# clock.net
KiCad netlist of a schematic drawn in Altium Designer
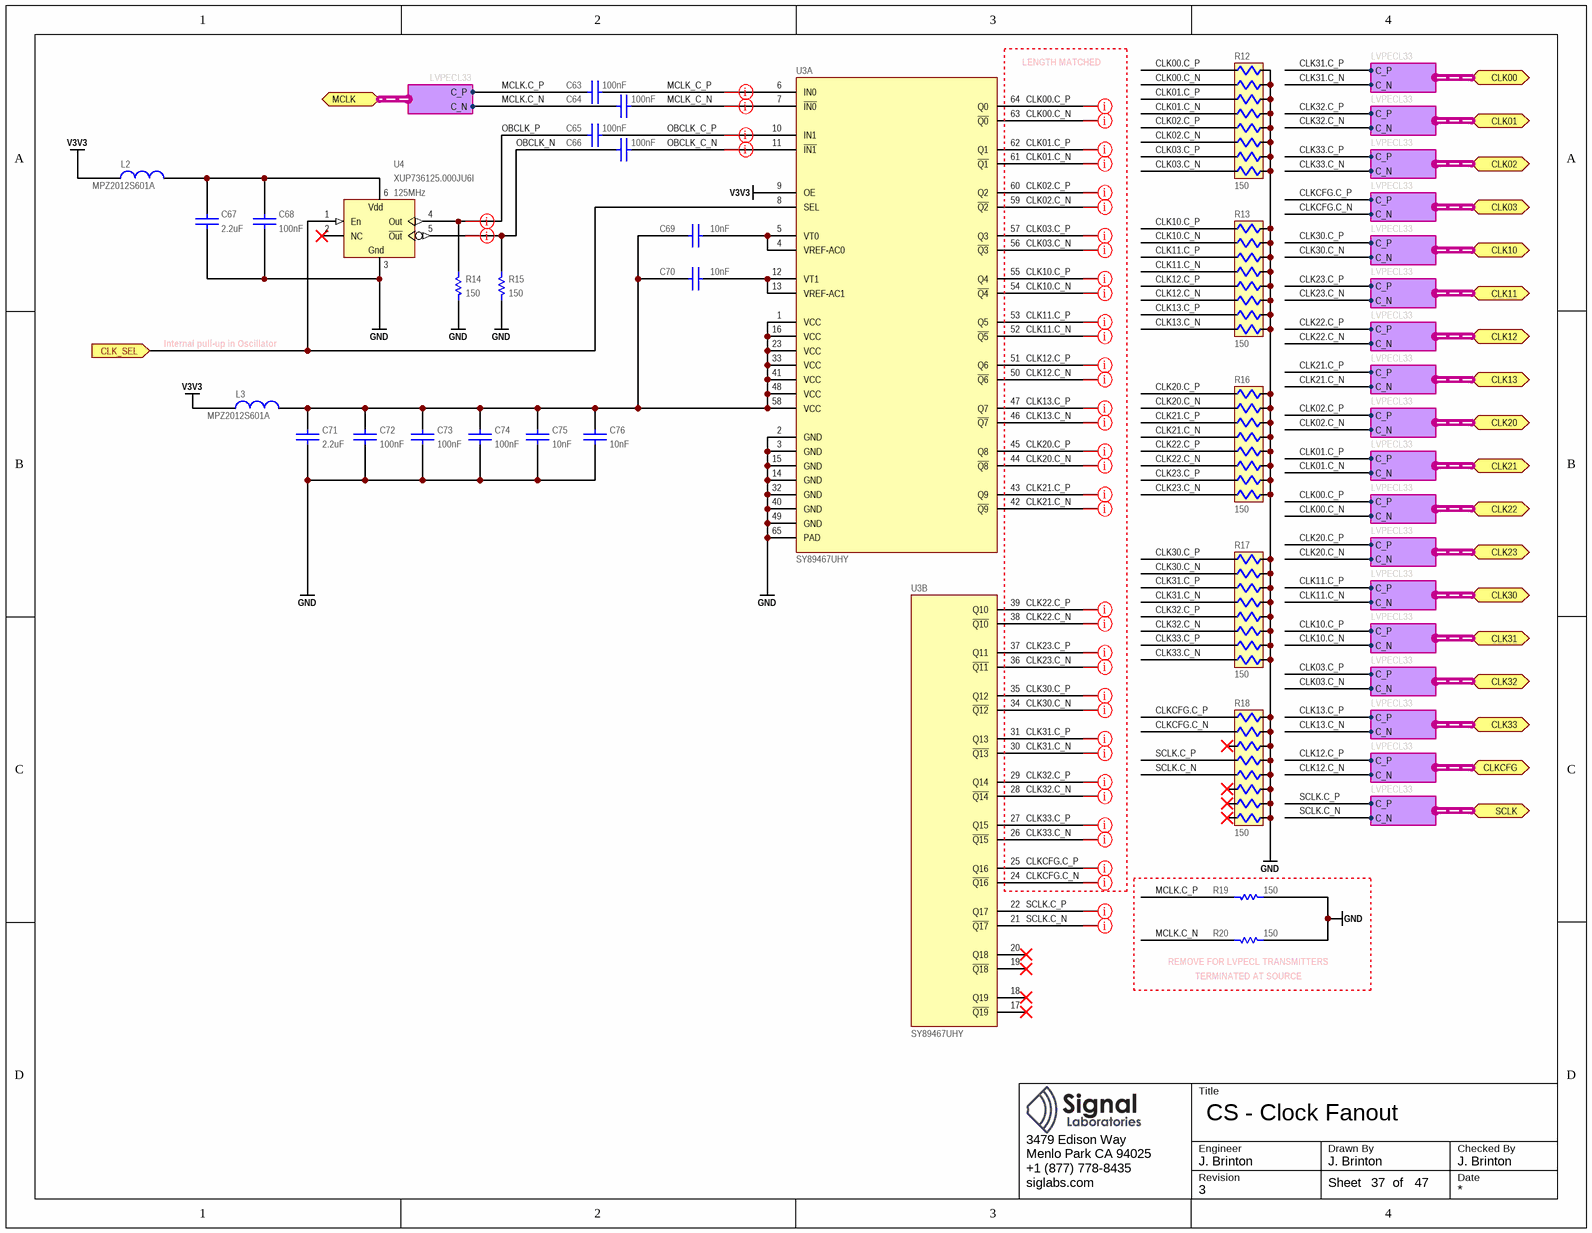
[diagram p0: clock.SchDoc]

(export (version "E")
  (design (tool "Eeschema 10.0.6"))
  (components
    (comp (ref "C63")
      (value "100nF")
      (footprint "CAPC100X50X55L25N")
      (description "Ceramic Capacitor 100nF ±10% 50V X7R 0402")
      (fields (field (name "MANUFACTURER") "Murata") (field (name "TOLERANCE") "±10%"))
      (libsource (lib "generic") (part "CAP"))
    )
    (comp (ref "C64")
      (value "100nF")
      (footprint "CAPC100X50X55L25N")
      (description "Ceramic Capacitor 100nF ±10% 50V X7R 0402")
      (fields (field (name "MANUFACTURER") "Murata") (field (name "TOLERANCE") "±10%"))
      (libsource (lib "generic") (part "CAP"))
    )
    (comp (ref "C65")
      (value "100nF")
      (footprint "CAPC100X50X55L25N")
      (description "Ceramic Capacitor 100nF ±10% 50V X7R 0402")
      (fields (field (name "MANUFACTURER") "Murata") (field (name "TOLERANCE") "±10%"))
      (libsource (lib "generic") (part "CAP"))
    )
    (comp (ref "C66")
      (value "100nF")
      (footprint "CAPC100X50X55L25N")
      (description "Ceramic Capacitor 100nF ±10% 50V X7R 0402")
      (fields (field (name "MANUFACTURER") "Murata") (field (name "TOLERANCE") "±10%"))
      (libsource (lib "generic") (part "CAP"))
    )
    (comp (ref "C67")
      (value "2.2uF")
      (footprint "CAPC160X80X90L20N")
      (description "Ceramic Capacitor 2.2uF ±20% 10V X7R 0603")
      (fields (field (name "MANUFACTURER") "TDK") (field (name "TOLERANCE") "±20%"))
      (libsource (lib "generic") (part "CAP"))
    )
    (comp (ref "C68")
      (value "100nF")
      (footprint "CAPC100X50X55L25N")
      (description "Ceramic Capacitor 100nF ±10% 50V X7R 0402")
      (fields (field (name "MANUFACTURER") "Murata") (field (name "TOLERANCE") "±10%"))
      (libsource (lib "generic") (part "CAP"))
    )
    (comp (ref "C69")
      (value "10nF")
      (footprint "CAPC100X50X55L25N")
      (description "Ceramic Capacitor 10nF ±10% 50V X7R 0402")
      (fields (field (name "MANUFACTURER") "Murata") (field (name "TOLERANCE") "±10%"))
      (libsource (lib "") (part "CAP_1"))
    )
    (comp (ref "C70")
      (value "10nF")
      (footprint "CAPC100X50X55L25N")
      (description "Ceramic Capacitor 10nF ±10% 50V X7R 0402")
      (fields (field (name "MANUFACTURER") "Murata") (field (name "TOLERANCE") "±10%"))
      (libsource (lib "") (part "CAP_1"))
    )
    (comp (ref "C71")
      (value "2.2uF")
      (footprint "CAPC160X80X90L20N")
      (description "Ceramic Capacitor 2.2uF ±20% 10V X7R 0603")
      (fields (field (name "MANUFACTURER") "TDK") (field (name "TOLERANCE") "±20%"))
      (libsource (lib "generic") (part "CAP"))
    )
    (comp (ref "C72")
      (value "100nF")
      (footprint "CAPC100X50X55L25N")
      (description "Ceramic Capacitor 100nF ±10% 50V X7R 0402")
      (fields (field (name "MANUFACTURER") "Murata") (field (name "TOLERANCE") "±10%"))
      (libsource (lib "generic") (part "CAP"))
    )
    (comp (ref "C73")
      (value "100nF")
      (footprint "CAPC100X50X55L25N")
      (description "Ceramic Capacitor 100nF ±10% 50V X7R 0402")
      (fields (field (name "MANUFACTURER") "Murata") (field (name "TOLERANCE") "±10%"))
      (libsource (lib "generic") (part "CAP"))
    )
    (comp (ref "C74")
      (value "100nF")
      (footprint "CAPC100X50X55L25N")
      (description "Ceramic Capacitor 100nF ±10% 50V X7R 0402")
      (fields (field (name "MANUFACTURER") "Murata") (field (name "TOLERANCE") "±10%"))
      (libsource (lib "generic") (part "CAP"))
    )
    (comp (ref "C75")
      (value "10nF")
      (footprint "CAPC100X50X55L25N")
      (description "Ceramic Capacitor 10nF ±10% 50V X7R 0402")
      (fields (field (name "MANUFACTURER") "Murata") (field (name "TOLERANCE") "±10%"))
      (libsource (lib "") (part "CAP_1"))
    )
    (comp (ref "C76")
      (value "10nF")
      (footprint "CAPC100X50X55L25N")
      (description "Ceramic Capacitor 10nF ±10% 50V X7R 0402")
      (fields (field (name "MANUFACTURER") "Murata") (field (name "TOLERANCE") "±10%"))
      (libsource (lib "") (part "CAP_1"))
    )
    (comp (ref "L2")
      (value "MPZ2012S601A")
      (footprint "0805")
      (description "Ferrite Bead 600-Ohm @ 100 MHz 2A 0805")
      (fields (field (name "MANUFACTURER") "TDK"))
      (libsource (lib "*") (part "INDUCTANCE1"))
    )
    (comp (ref "L3")
      (value "MPZ2012S601A")
      (footprint "0805")
      (description "Ferrite Bead 600-Ohm @ 100 MHz 2A 0805")
      (fields (field (name "MANUFACTURER") "TDK"))
      (libsource (lib "*") (part "INDUCTANCE1"))
    )
    (comp (ref "R12")
      (value "150")
      (footprint "RESCAXE16P50_380X160X55L30X35N")
      (description "8 Resistor Array 150 ±5% 0.0625W 25V 1506")
      (fields (field (name "MANUFACTURER") "Panasonic") (field (name "TOLERANCE") "±5%"))
      (libsource (lib "altium-import") (part "root_0_EXB-2HV470JV_"))
    )
    (comp (ref "R13")
      (value "150")
      (footprint "RESCAXE16P50_380X160X55L30X35N")
      (description "8 Resistor Array 150 ±5% 0.0625W 25V 1506")
      (fields (field (name "MANUFACTURER") "Panasonic") (field (name "TOLERANCE") "±5%"))
      (libsource (lib "altium-import") (part "root_0_EXB-2HV470JV_"))
    )
    (comp (ref "R14")
      (value "150")
      (footprint "RESC1005X40N")
      (description "Thick Film Resistor 150 ±1% 0.1W 50V 0402")
      (fields (field (name "TOLERANCE") "±1%") (field (name "MANUFACTURER") "Panasonic"))
      (libsource (lib "generic") (part "RES"))
    )
    (comp (ref "R15")
      (value "150")
      (footprint "RESC1005X40N")
      (description "Thick Film Resistor 150 ±1% 0.1W 50V 0402")
      (fields (field (name "TOLERANCE") "±1%") (field (name "MANUFACTURER") "Panasonic"))
      (libsource (lib "generic") (part "RES"))
    )
    (comp (ref "R16")
      (value "150")
      (footprint "RESCAXE16P50_380X160X55L30X35N")
      (description "8 Resistor Array 150 ±5% 0.0625W 25V 1506")
      (fields (field (name "MANUFACTURER") "Panasonic") (field (name "TOLERANCE") "±5%"))
      (libsource (lib "altium-import") (part "root_0_EXB-2HV470JV_"))
    )
    (comp (ref "R17")
      (value "150")
      (footprint "RESCAXE16P50_380X160X55L30X35N")
      (description "8 Resistor Array 150 ±5% 0.0625W 25V 1506")
      (fields (field (name "MANUFACTURER") "Panasonic") (field (name "TOLERANCE") "±5%"))
      (libsource (lib "altium-import") (part "root_0_EXB-2HV470JV_"))
    )
    (comp (ref "R18")
      (value "150")
      (footprint "RESCAXE16P50_380X160X55L30X35N")
      (description "8 Resistor Array 150 ±5% 0.0625W 25V 1506")
      (fields (field (name "MANUFACTURER") "Panasonic") (field (name "TOLERANCE") "±5%"))
      (libsource (lib "altium-import") (part "root_0_EXB-2HV470JV_"))
    )
    (comp (ref "R19")
      (value "150")
      (footprint "RESC1005X40N")
      (description "Thick Film Resistor 150 ±1% 0.1W 50V 0402")
      (fields (field (name "TOLERANCE") "±1%") (field (name "MANUFACTURER") "Panasonic"))
      (libsource (lib "generic") (part "RES"))
    )
    (comp (ref "R20")
      (value "150")
      (footprint "RESC1005X40N")
      (description "Thick Film Resistor 150 ±1% 0.1W 50V 0402")
      (fields (field (name "TOLERANCE") "±1%") (field (name "MANUFACTURER") "Panasonic"))
      (libsource (lib "generic") (part "RES"))
    )
    (comp (ref "U3")
      (value "SY89467UHY")
      (footprint "QFP65P50_1200X1200X120L60X22T500N")
      (description "2:20 LVPECL Clock Distribution Driver")
      (fields (field (name "MANUFACTURER") "Microchip"))
      (libsource (lib "microchip") (part "SY89467UHY"))
    )
    (comp (ref "U4")
      (value "125MHz")
      (footprint "fox:OSCSC6P254_735X505X140L110X140")
      (description "Oscillator 100MHz LPECL 3.3V 25ppm SMD")
      (fields
        (field (name "MANUFACTURER") "IDT")
        (field (name "MANUFACTURER P/N") "XUP736125.000JU6I")
        (field (name "Comment") "XUP736125.000JU6I")
      )
      (libsource (lib "seiko") (part "EG-2121CA 100.0000M-PHPAB"))
    )
  )
  (nets
    (net (code "2") (name "/CLK00.C_N") (class "Default")
      (node (ref "R12") (pin "2") (pinfunction "2_2") (pintype "passive"))
      (node (ref "U3") (pin "63") (pinfunction "~{Q0}_63") (pintype "passive"))
    )
    (net (code "3") (name "/CLK00.C_P") (class "Default")
      (node (ref "R12") (pin "1") (pintype "passive"))
      (node (ref "U3") (pin "64") (pinfunction "Q0_64") (pintype "passive"))
    )
    (net (code "4") (name "/CLK01.C_N") (class "Default")
      (node (ref "R12") (pin "4") (pinfunction "4_4") (pintype "passive"))
      (node (ref "U3") (pin "61") (pinfunction "~{Q1}_61") (pintype "passive"))
    )
    (net (code "5") (name "/CLK01.C_P") (class "Default")
      (node (ref "R12") (pin "3") (pinfunction "3_3") (pintype "passive"))
      (node (ref "U3") (pin "62") (pinfunction "Q1_62") (pintype "passive"))
    )
    (net (code "6") (name "/CLK02.C_N") (class "Default")
      (node (ref "R12") (pin "6") (pinfunction "6_6") (pintype "passive"))
      (node (ref "U3") (pin "59") (pinfunction "~{Q2}_59") (pintype "passive"))
    )
    (net (code "7") (name "/CLK02.C_P") (class "Default")
      (node (ref "R12") (pin "5") (pinfunction "5_5") (pintype "passive"))
      (node (ref "U3") (pin "60") (pinfunction "Q2_60") (pintype "passive"))
    )
    (net (code "8") (name "/CLK03.C_N") (class "Default")
      (node (ref "R12") (pin "8") (pinfunction "8_8") (pintype "passive"))
      (node (ref "U3") (pin "56") (pinfunction "~{Q3}_56") (pintype "passive"))
    )
    (net (code "9") (name "/CLK03.C_P") (class "Default")
      (node (ref "R12") (pin "7") (pinfunction "7_7") (pintype "passive"))
      (node (ref "U3") (pin "57") (pinfunction "Q3_57") (pintype "passive"))
    )
    (net (code "10") (name "/CLK10.C_N") (class "Default")
      (node (ref "R13") (pin "2") (pinfunction "2_2") (pintype "passive"))
      (node (ref "U3") (pin "54") (pinfunction "~{Q4}_54") (pintype "passive"))
    )
    (net (code "11") (name "/CLK10.C_P") (class "Default")
      (node (ref "R13") (pin "1") (pintype "passive"))
      (node (ref "U3") (pin "55") (pinfunction "Q4_55") (pintype "passive"))
    )
    (net (code "12") (name "/CLK11.C_N") (class "Default")
      (node (ref "R13") (pin "4") (pinfunction "4_4") (pintype "passive"))
      (node (ref "U3") (pin "52") (pinfunction "~{Q5}_52") (pintype "passive"))
    )
    (net (code "13") (name "/CLK11.C_P") (class "Default")
      (node (ref "R13") (pin "3") (pinfunction "3_3") (pintype "passive"))
      (node (ref "U3") (pin "53") (pinfunction "Q5_53") (pintype "passive"))
    )
    (net (code "14") (name "/CLK12.C_N") (class "Default")
      (node (ref "R13") (pin "6") (pinfunction "6_6") (pintype "passive"))
      (node (ref "U3") (pin "50") (pinfunction "~{Q6}_50") (pintype "passive"))
    )
    (net (code "15") (name "/CLK12.C_P") (class "Default")
      (node (ref "R13") (pin "5") (pinfunction "5_5") (pintype "passive"))
      (node (ref "U3") (pin "51") (pinfunction "Q6_51") (pintype "passive"))
    )
    (net (code "16") (name "/CLK13.C_N") (class "Default")
      (node (ref "R13") (pin "8") (pinfunction "8_8") (pintype "passive"))
      (node (ref "U3") (pin "46") (pinfunction "~{Q7}_46") (pintype "passive"))
    )
    (net (code "17") (name "/CLK13.C_P") (class "Default")
      (node (ref "R13") (pin "7") (pinfunction "7_7") (pintype "passive"))
      (node (ref "U3") (pin "47") (pinfunction "Q7_47") (pintype "passive"))
    )
    (net (code "18") (name "/CLK20.C_N") (class "Default")
      (node (ref "R16") (pin "2") (pinfunction "2_2") (pintype "passive"))
      (node (ref "U3") (pin "44") (pinfunction "~{Q8}_44") (pintype "passive"))
    )
    (net (code "19") (name "/CLK20.C_P") (class "Default")
      (node (ref "R16") (pin "1") (pintype "passive"))
      (node (ref "U3") (pin "45") (pinfunction "Q8_45") (pintype "passive"))
    )
    (net (code "20") (name "/CLK21.C_N") (class "Default")
      (node (ref "R16") (pin "4") (pinfunction "4_4") (pintype "passive"))
      (node (ref "U3") (pin "42") (pinfunction "~{Q9}_42") (pintype "passive"))
    )
    (net (code "21") (name "/CLK21.C_P") (class "Default")
      (node (ref "R16") (pin "3") (pinfunction "3_3") (pintype "passive"))
      (node (ref "U3") (pin "43") (pinfunction "Q9_43") (pintype "passive"))
    )
    (net (code "22") (name "/CLK22.C_N") (class "Default")
      (node (ref "R16") (pin "6") (pinfunction "6_6") (pintype "passive"))
      (node (ref "U3") (pin "38") (pinfunction "~{Q10}_38") (pintype "passive"))
    )
    (net (code "23") (name "/CLK22.C_P") (class "Default")
      (node (ref "R16") (pin "5") (pinfunction "5_5") (pintype "passive"))
      (node (ref "U3") (pin "39") (pinfunction "Q10_39") (pintype "passive"))
    )
    (net (code "24") (name "/CLK23.C_N") (class "Default")
      (node (ref "R16") (pin "8") (pinfunction "8_8") (pintype "passive"))
      (node (ref "U3") (pin "36") (pinfunction "~{Q11}_36") (pintype "passive"))
    )
    (net (code "25") (name "/CLK23.C_P") (class "Default")
      (node (ref "R16") (pin "7") (pinfunction "7_7") (pintype "passive"))
      (node (ref "U3") (pin "37") (pinfunction "Q11_37") (pintype "passive"))
    )
    (net (code "26") (name "/CLK30.C_N") (class "Default")
      (node (ref "R17") (pin "2") (pinfunction "2_2") (pintype "passive"))
      (node (ref "U3") (pin "34") (pinfunction "~{Q12}_34") (pintype "passive"))
    )
    (net (code "27") (name "/CLK30.C_P") (class "Default")
      (node (ref "R17") (pin "1") (pintype "passive"))
      (node (ref "U3") (pin "35") (pinfunction "Q12_35") (pintype "passive"))
    )
    (net (code "28") (name "/CLK31.C_N") (class "Default")
      (node (ref "R17") (pin "4") (pinfunction "4_4") (pintype "passive"))
      (node (ref "U3") (pin "30") (pinfunction "~{Q13}_30") (pintype "passive"))
    )
    (net (code "29") (name "/CLK31.C_P") (class "Default")
      (node (ref "R17") (pin "3") (pinfunction "3_3") (pintype "passive"))
      (node (ref "U3") (pin "31") (pinfunction "Q13_31") (pintype "passive"))
    )
    (net (code "30") (name "/CLK32.C_N") (class "Default")
      (node (ref "R17") (pin "6") (pinfunction "6_6") (pintype "passive"))
      (node (ref "U3") (pin "28") (pinfunction "~{Q14}_28") (pintype "passive"))
    )
    (net (code "31") (name "/CLK32.C_P") (class "Default")
      (node (ref "R17") (pin "5") (pinfunction "5_5") (pintype "passive"))
      (node (ref "U3") (pin "29") (pinfunction "Q14_29") (pintype "passive"))
    )
    (net (code "32") (name "/CLK33.C_N") (class "Default")
      (node (ref "R17") (pin "8") (pinfunction "8_8") (pintype "passive"))
      (node (ref "U3") (pin "26") (pinfunction "~{Q15}_26") (pintype "passive"))
    )
    (net (code "33") (name "/CLK33.C_P") (class "Default")
      (node (ref "R17") (pin "7") (pinfunction "7_7") (pintype "passive"))
      (node (ref "U3") (pin "27") (pinfunction "Q15_27") (pintype "passive"))
    )
    (net (code "34") (name "/CLKCFG.C_N") (class "Default")
      (node (ref "R18") (pin "2") (pinfunction "2_2") (pintype "passive"))
      (node (ref "U3") (pin "24") (pinfunction "~{Q16}_24") (pintype "passive"))
    )
    (net (code "35") (name "/CLKCFG.C_P") (class "Default")
      (node (ref "R18") (pin "1") (pintype "passive"))
      (node (ref "U3") (pin "25") (pinfunction "Q16_25") (pintype "passive"))
    )
    (net (code "36") (name "/CLK_SEL") (class "Default")
      (node (ref "U3") (pin "8") (pinfunction "SEL_8") (pintype "passive"))
      (node (ref "U4") (pin "1") (pinfunction "En_1") (pintype "input"))
    )
    (net (code "37") (name "/MCLK.C_N") (class "Default")
      (node (ref "C64") (pin "2") (pinfunction "2_2") (pintype "passive"))
      (node (ref "R20") (pin "1") (pinfunction "1_1") (pintype "passive"))
    )
    (net (code "38") (name "/MCLK.C_P") (class "Default")
      (node (ref "C63") (pin "2") (pinfunction "2_2") (pintype "passive"))
      (node (ref "R19") (pin "1") (pinfunction "1_1") (pintype "passive"))
    )
    (net (code "39") (name "/MCLK_C_N") (class "Default")
      (node (ref "C64") (pin "1") (pinfunction "1_1") (pintype "passive"))
      (node (ref "U3") (pin "7") (pinfunction "~{IN0}_7") (pintype "passive"))
    )
    (net (code "40") (name "/MCLK_C_P") (class "Default")
      (node (ref "C63") (pin "1") (pinfunction "1_1") (pintype "passive"))
      (node (ref "U3") (pin "6") (pinfunction "IN0_6") (pintype "passive"))
    )
    (net (code "41") (name "/OBCLK_C_N") (class "Default")
      (node (ref "C66") (pin "1") (pinfunction "1_1") (pintype "passive"))
      (node (ref "U3") (pin "11") (pinfunction "~{IN1}_11") (pintype "passive"))
    )
    (net (code "42") (name "/OBCLK_C_P") (class "Default")
      (node (ref "C65") (pin "1") (pinfunction "1_1") (pintype "passive"))
      (node (ref "U3") (pin "10") (pinfunction "IN1_10") (pintype "passive"))
    )
    (net (code "43") (name "/OBCLK_N") (class "Default")
      (node (ref "C66") (pin "2") (pinfunction "2_2") (pintype "passive"))
      (node (ref "R15") (pin "2") (pinfunction "2_2") (pintype "passive"))
      (node (ref "U4") (pin "5") (pinfunction "~{Out}_5") (pintype "output"))
    )
    (net (code "44") (name "/OBCLK_P") (class "Default")
      (node (ref "C65") (pin "2") (pinfunction "2_2") (pintype "passive"))
      (node (ref "R14") (pin "2") (pinfunction "2_2") (pintype "passive"))
      (node (ref "U4") (pin "4") (pinfunction "Out_4") (pintype "output"))
    )
    (net (code "45") (name "/SCLK.C_N") (class "Default")
      (node (ref "R18") (pin "5") (pinfunction "5_5") (pintype "passive"))
      (node (ref "U3") (pin "21") (pinfunction "~{Q17}_21") (pintype "passive"))
    )
    (net (code "46") (name "/SCLK.C_P") (class "Default")
      (node (ref "R18") (pin "4") (pinfunction "4_4") (pintype "passive"))
      (node (ref "U3") (pin "22") (pinfunction "Q17_22") (pintype "passive"))
    )
    (net (code "48") (name "GND") (class "Default")
      (node (ref "C67") (pin "1") (pinfunction "1_1") (pintype "passive"))
      (node (ref "C68") (pin "1") (pinfunction "1_1") (pintype "passive"))
      (node (ref "C71") (pin "1") (pinfunction "1_1") (pintype "passive"))
      (node (ref "C72") (pin "1") (pinfunction "1_1") (pintype "passive"))
      (node (ref "C73") (pin "1") (pinfunction "1_1") (pintype "passive"))
      (node (ref "C74") (pin "1") (pinfunction "1_1") (pintype "passive"))
      (node (ref "C75") (pin "2") (pinfunction "2_2") (pintype "passive"))
      (node (ref "C76") (pin "2") (pinfunction "2_2") (pintype "passive"))
      (node (ref "R12") (pin "10") (pinfunction "10_10") (pintype "passive"))
      (node (ref "R12") (pin "11") (pinfunction "11_11") (pintype "passive"))
      (node (ref "R12") (pin "12") (pinfunction "12_12") (pintype "passive"))
      (node (ref "R12") (pin "13") (pinfunction "13_13") (pintype "passive"))
      (node (ref "R12") (pin "14") (pinfunction "14_14") (pintype "passive"))
      (node (ref "R12") (pin "15") (pinfunction "15_15") (pintype "passive"))
      (node (ref "R12") (pin "16") (pinfunction "16_16") (pintype "passive"))
      (node (ref "R12") (pin "9") (pinfunction "9_9") (pintype "passive"))
      (node (ref "R13") (pin "10") (pinfunction "10_10") (pintype "passive"))
      (node (ref "R13") (pin "11") (pinfunction "11_11") (pintype "passive"))
      (node (ref "R13") (pin "12") (pinfunction "12_12") (pintype "passive"))
      (node (ref "R13") (pin "13") (pinfunction "13_13") (pintype "passive"))
      (node (ref "R13") (pin "14") (pinfunction "14_14") (pintype "passive"))
      (node (ref "R13") (pin "15") (pinfunction "15_15") (pintype "passive"))
      (node (ref "R13") (pin "16") (pinfunction "16_16") (pintype "passive"))
      (node (ref "R13") (pin "9") (pinfunction "9_9") (pintype "passive"))
      (node (ref "R14") (pin "1") (pinfunction "1_1") (pintype "passive"))
      (node (ref "R15") (pin "1") (pinfunction "1_1") (pintype "passive"))
      (node (ref "R16") (pin "10") (pinfunction "10_10") (pintype "passive"))
      (node (ref "R16") (pin "11") (pinfunction "11_11") (pintype "passive"))
      (node (ref "R16") (pin "12") (pinfunction "12_12") (pintype "passive"))
      (node (ref "R16") (pin "13") (pinfunction "13_13") (pintype "passive"))
      (node (ref "R16") (pin "14") (pinfunction "14_14") (pintype "passive"))
      (node (ref "R16") (pin "15") (pinfunction "15_15") (pintype "passive"))
      (node (ref "R16") (pin "16") (pinfunction "16_16") (pintype "passive"))
      (node (ref "R16") (pin "9") (pinfunction "9_9") (pintype "passive"))
      (node (ref "R17") (pin "10") (pinfunction "10_10") (pintype "passive"))
      (node (ref "R17") (pin "11") (pinfunction "11_11") (pintype "passive"))
      (node (ref "R17") (pin "12") (pinfunction "12_12") (pintype "passive"))
      (node (ref "R17") (pin "13") (pinfunction "13_13") (pintype "passive"))
      (node (ref "R17") (pin "14") (pinfunction "14_14") (pintype "passive"))
      (node (ref "R17") (pin "15") (pinfunction "15_15") (pintype "passive"))
      (node (ref "R17") (pin "16") (pinfunction "16_16") (pintype "passive"))
      (node (ref "R17") (pin "9") (pinfunction "9_9") (pintype "passive"))
      (node (ref "R18") (pin "10") (pinfunction "10_10") (pintype "passive"))
      (node (ref "R18") (pin "11") (pinfunction "11_11") (pintype "passive"))
      (node (ref "R18") (pin "12") (pinfunction "12_12") (pintype "passive"))
      (node (ref "R18") (pin "13") (pinfunction "13_13") (pintype "passive"))
      (node (ref "R18") (pin "14") (pinfunction "14_14") (pintype "passive"))
      (node (ref "R18") (pin "15") (pinfunction "15_15") (pintype "passive"))
      (node (ref "R18") (pin "16") (pinfunction "16_16") (pintype "passive"))
      (node (ref "R18") (pin "9") (pinfunction "9_9") (pintype "passive"))
      (node (ref "R19") (pin "2") (pinfunction "2_2") (pintype "passive"))
      (node (ref "R20") (pin "2") (pinfunction "2_2") (pintype "passive"))
      (node (ref "U3") (pin "14") (pinfunction "GND_14") (pintype "passive"))
      (node (ref "U3") (pin "15") (pinfunction "GND_15") (pintype "passive"))
      (node (ref "U3") (pin "2") (pinfunction "GND_2") (pintype "passive"))
      (node (ref "U3") (pin "3") (pinfunction "GND_3") (pintype "passive"))
      (node (ref "U3") (pin "32") (pinfunction "GND_32") (pintype "passive"))
      (node (ref "U3") (pin "40") (pinfunction "GND_40") (pintype "passive"))
      (node (ref "U3") (pin "49") (pinfunction "GND_49") (pintype "passive"))
      (node (ref "U3") (pin "65") (pinfunction "PAD_65") (pintype "passive"))
      (node (ref "U4") (pin "3") (pinfunction "GND_3") (pintype "power_in"))
    )
    (net (code "49") (name "Net-(C69-Pad1)") (class "Default")
      (node (ref "C69") (pin "1") (pinfunction "1_1") (pintype "passive"))
      (node (ref "C70") (pin "1") (pinfunction "1_1") (pintype "passive"))
      (node (ref "C71") (pin "2") (pinfunction "2_2") (pintype "passive"))
      (node (ref "C72") (pin "2") (pinfunction "2_2") (pintype "passive"))
      (node (ref "C73") (pin "2") (pinfunction "2_2") (pintype "passive"))
      (node (ref "C74") (pin "2") (pinfunction "2_2") (pintype "passive"))
      (node (ref "C75") (pin "1") (pinfunction "1_1") (pintype "passive"))
      (node (ref "C76") (pin "1") (pinfunction "1_1") (pintype "passive"))
      (node (ref "L3") (pin "1") (pinfunction "1_1") (pintype "passive"))
      (node (ref "U3") (pin "1") (pinfunction "VCC_1") (pintype "passive"))
      (node (ref "U3") (pin "16") (pinfunction "VCC_16") (pintype "passive"))
      (node (ref "U3") (pin "23") (pinfunction "VCC_23") (pintype "passive"))
      (node (ref "U3") (pin "33") (pinfunction "VCC_33") (pintype "passive"))
      (node (ref "U3") (pin "41") (pinfunction "VCC_41") (pintype "passive"))
      (node (ref "U3") (pin "48") (pinfunction "VCC_48") (pintype "passive"))
      (node (ref "U3") (pin "58") (pinfunction "VCC_58") (pintype "passive"))
    )
    (net (code "50") (name "Net-(U3A-VREF-AC0)") (class "Default")
      (node (ref "C69") (pin "2") (pinfunction "2_2") (pintype "passive"))
      (node (ref "U3") (pin "4") (pinfunction "VREF-AC0_4") (pintype "passive"))
      (node (ref "U3") (pin "5") (pinfunction "VT0_5") (pintype "passive"))
    )
    (net (code "51") (name "Net-(U3A-VREF-AC1)") (class "Default")
      (node (ref "C70") (pin "2") (pinfunction "2_2") (pintype "passive"))
      (node (ref "U3") (pin "12") (pinfunction "VT1_12") (pintype "passive"))
      (node (ref "U3") (pin "13") (pinfunction "VREF-AC1_13") (pintype "passive"))
    )
    (net (code "52") (name "Net-(U4-Vdd)") (class "Default")
      (node (ref "C67") (pin "2") (pinfunction "2_2") (pintype "passive"))
      (node (ref "C68") (pin "2") (pinfunction "2_2") (pintype "passive"))
      (node (ref "L2") (pin "1") (pinfunction "1_1") (pintype "passive"))
      (node (ref "U4") (pin "6") (pinfunction "Vdd_6") (pintype "power_in"))
    )
    (net (code "53") (name "V3V3") (class "Default")
      (node (ref "L2") (pin "2") (pinfunction "2_2") (pintype "passive"))
      (node (ref "L3") (pin "2") (pinfunction "2_2") (pintype "passive"))
      (node (ref "U3") (pin "9") (pinfunction "OE_9") (pintype "passive"))
    )
    (net (code "54") (name "unconnected-(R18-Pad3)") (class "Default")
      (node (ref "R18") (pin "3") (pinfunction "3_3") (pintype "passive+no_connect"))
    )
    (net (code "55") (name "unconnected-(R18-Pad6)") (class "Default")
      (node (ref "R18") (pin "6") (pinfunction "6_6") (pintype "passive+no_connect"))
    )
    (net (code "56") (name "unconnected-(R18-Pad7)") (class "Default")
      (node (ref "R18") (pin "7") (pinfunction "7_7") (pintype "passive+no_connect"))
    )
    (net (code "57") (name "unconnected-(R18-Pad8)") (class "Default")
      (node (ref "R18") (pin "8") (pinfunction "8_8") (pintype "passive+no_connect"))
    )
    (net (code "58") (name "unconnected-(U3B-Q18-Pad20)") (class "Default")
      (node (ref "U3") (pin "20") (pinfunction "Q18_20") (pintype "passive+no_connect"))
    )
    (net (code "59") (name "unconnected-(U3B-Q19-Pad18)") (class "Default")
      (node (ref "U3") (pin "18") (pinfunction "Q19_18") (pintype "passive+no_connect"))
    )
    (net (code "60") (name "unconnected-(U3B-~{Q18}-Pad19)") (class "Default")
      (node (ref "U3") (pin "19") (pinfunction "~{Q18}_19") (pintype "passive+no_connect"))
    )
    (net (code "61") (name "unconnected-(U3B-~{Q19}-Pad17)") (class "Default")
      (node (ref "U3") (pin "17") (pinfunction "~{Q19}_17") (pintype "passive+no_connect"))
    )
    (net (code "62") (name "unconnected-(U4-NC-Pad2)") (class "Default")
      (node (ref "U4") (pin "2") (pinfunction "NC_2") (pintype "passive+no_connect"))
    )
  )
)
